# OmniLight.net
KiCad netlist of a schematic drawn in EAGLE
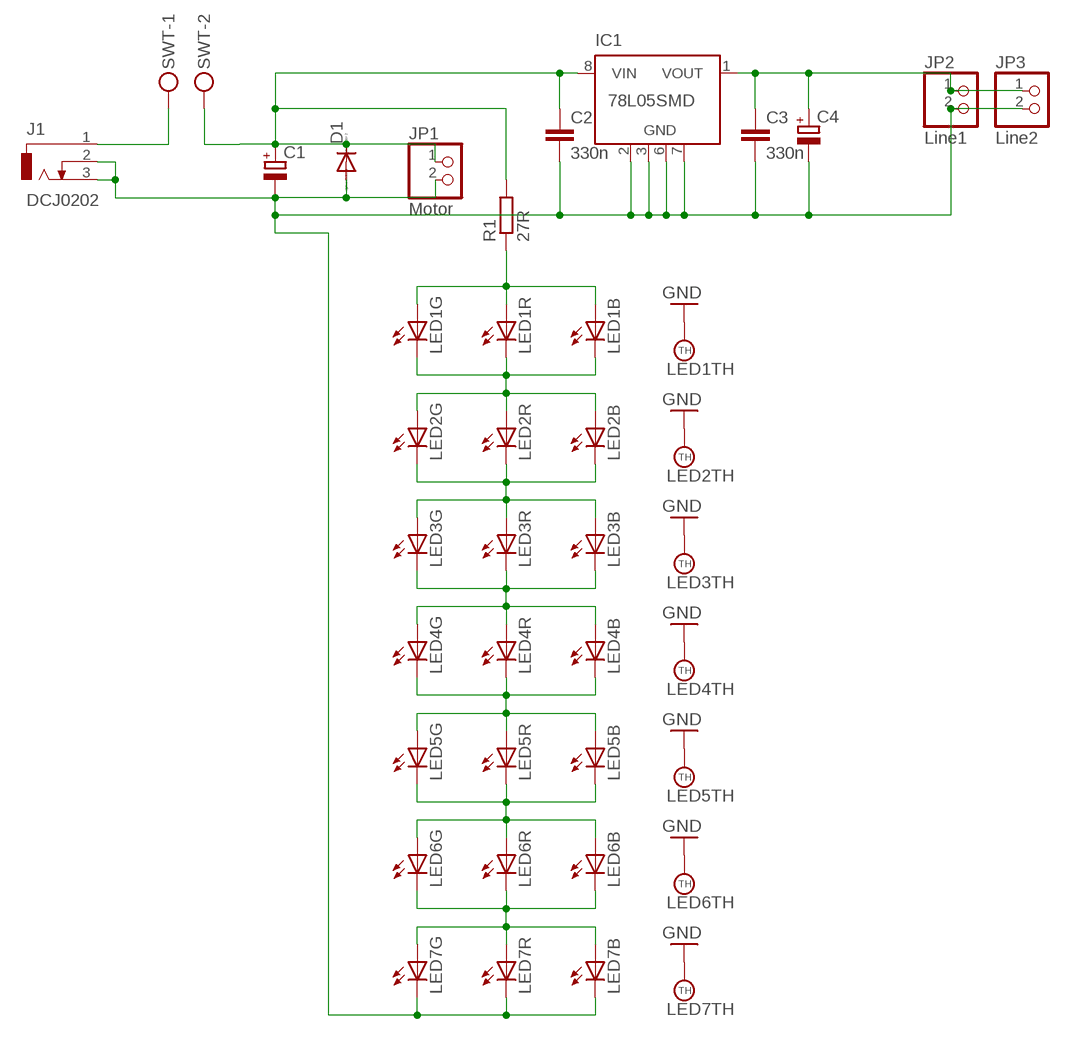
[diagram p0: schematic, sheet 1]

(export (version "E")
  (design (tool "Eeschema 10.0.6"))
  (components
    (comp (ref "C1")
      (value "CPOL-EU140CLH-0810")
      (footprint "eagle-import:140CLH-0810")
      (libsource (lib "eagle-import") (part "CPOL-EU140CLH-0810"))
    )
    (comp (ref "C2")
      (value "330n")
      (footprint "eagle-import:C1206")
      (libsource (lib "eagle-import") (part "C-EUC1206"))
    )
    (comp (ref "C3")
      (value "330n")
      (footprint "eagle-import:C1206")
      (libsource (lib "eagle-import") (part "C-EUC1206"))
    )
    (comp (ref "C4")
      (value "CPOL-EU140CLH-0810")
      (footprint "eagle-import:140CLH-0810")
      (libsource (lib "eagle-import") (part "CPOL-EU140CLH-0810"))
    )
    (comp (ref "D1")
      (value "DIODE-DO214AC")
      (footprint "eagle-import:DO214AC")
      (libsource (lib "eagle-import") (part "DIODE-DO214AC"))
    )
    (comp (ref "IC1")
      (value "78L05SMD")
      (footprint "eagle-import:SO08")
      (libsource (lib "eagle-import") (part "78LSMD05"))
    )
    (comp (ref "J1")
      (value "DCJ0202")
      (footprint "eagle-import:DCJ0202")
      (libsource (lib "eagle-import") (part "DCJ0202"))
    )
    (comp (ref "JP1")
      (value "Motor")
      (footprint "eagle-import:1X02")
      (libsource (lib "eagle-import") (part "PINHD-1X2"))
    )
    (comp (ref "JP2")
      (value "Line1")
      (footprint "eagle-import:1X02")
      (libsource (lib "eagle-import") (part "PINHD-1X2"))
    )
    (comp (ref "JP3")
      (value "Line2")
      (footprint "eagle-import:1X02")
      (libsource (lib "eagle-import") (part "PINHD-1X2"))
    )
    (comp (ref "LED1")
      (value "LP2C63-ST-RGB-SR0")
      (footprint "eagle-import:LP2C63-ST-RGB-SR0")
      (libsource (lib "eagle-import") (part "LP2C63-ST-RGB-SR0"))
    )
    (comp (ref "LED2")
      (value "LP2C63-ST-RGB-SR0")
      (footprint "eagle-import:LP2C63-ST-RGB-SR0")
      (libsource (lib "eagle-import") (part "LP2C63-ST-RGB-SR0"))
    )
    (comp (ref "LED3")
      (value "LP2C63-ST-RGB-SR0")
      (footprint "eagle-import:LP2C63-ST-RGB-SR0")
      (libsource (lib "eagle-import") (part "LP2C63-ST-RGB-SR0"))
    )
    (comp (ref "LED4")
      (value "LP2C63-ST-RGB-SR0")
      (footprint "eagle-import:LP2C63-ST-RGB-SR0")
      (libsource (lib "eagle-import") (part "LP2C63-ST-RGB-SR0"))
    )
    (comp (ref "LED5")
      (value "LP2C63-ST-RGB-SR0")
      (footprint "eagle-import:LP2C63-ST-RGB-SR0")
      (libsource (lib "eagle-import") (part "LP2C63-ST-RGB-SR0"))
    )
    (comp (ref "LED6")
      (value "LP2C63-ST-RGB-SR0")
      (footprint "eagle-import:LP2C63-ST-RGB-SR0")
      (libsource (lib "eagle-import") (part "LP2C63-ST-RGB-SR0"))
    )
    (comp (ref "LED7")
      (value "LP2C63-ST-RGB-SR0")
      (footprint "eagle-import:LP2C63-ST-RGB-SR0")
      (libsource (lib "eagle-import") (part "LP2C63-ST-RGB-SR0"))
    )
    (comp (ref "R1")
      (value "27R")
      (footprint "eagle-import:R1206")
      (libsource (lib "eagle-import") (part "R-EU_R1206"))
    )
    (comp (ref "SWT")
      (value "MKDSN1,5/2-5,08")
      (footprint "eagle-import:MKDSN1,5_2-5,08")
      (libsource (lib "eagle-import") (part "MKDSN1,5/2-5,08"))
    )
  )
  (nets
    (net (code "1") (name "GND") (class "Default")
      (node (ref "LED1") (pin "TH") (pinfunction "TH_TH") (pintype "passive"))
      (node (ref "LED2") (pin "TH") (pinfunction "TH_TH") (pintype "passive"))
      (node (ref "LED3") (pin "TH") (pinfunction "TH_TH") (pintype "passive"))
      (node (ref "LED4") (pin "TH") (pinfunction "TH_TH") (pintype "passive"))
      (node (ref "LED5") (pin "TH") (pinfunction "TH_TH") (pintype "passive"))
      (node (ref "LED6") (pin "TH") (pinfunction "TH_TH") (pintype "passive"))
      (node (ref "LED7") (pin "TH") (pinfunction "TH_TH") (pintype "passive"))
    )
    (net (code "2") (name "Net-(IC1A-VIN)") (class "Default")
      (node (ref "C1") (pin "+") (pinfunction "+_+") (pintype "passive"))
      (node (ref "C2") (pin "1") (pinfunction "1_1") (pintype "passive"))
      (node (ref "D1") (pin "C") (pinfunction "C_C") (pintype "passive"))
      (node (ref "IC1") (pin "8") (pinfunction "VIN_8") (pintype "passive"))
      (node (ref "JP1") (pin "1") (pinfunction "1_1") (pintype "passive"))
      (node (ref "R1") (pin "2") (pinfunction "2_2") (pintype "passive"))
      (node (ref "SWT") (pin "2") (pinfunction "KL_2") (pintype "passive"))
    )
    (net (code "3") (name "Net-(IC1A-VOUT)") (class "Default")
      (node (ref "C3") (pin "1") (pinfunction "1_1") (pintype "passive"))
      (node (ref "C4") (pin "+") (pinfunction "+_+") (pintype "passive"))
      (node (ref "IC1") (pin "1") (pinfunction "VOUT_1") (pintype "output"))
      (node (ref "JP2") (pin "1") (pinfunction "1_1") (pintype "passive"))
      (node (ref "JP3") (pin "1") (pinfunction "1_1") (pintype "passive"))
    )
    (net (code "4") (name "Net-(LED1A-A)") (class "Default")
      (node (ref "LED1") (pin "1") (pinfunction "A_1") (pintype "passive"))
      (node (ref "LED1") (pin "2") (pinfunction "A_2") (pintype "passive"))
      (node (ref "LED1") (pin "3") (pinfunction "A_3") (pintype "passive"))
      (node (ref "R1") (pin "1") (pinfunction "1_1") (pintype "passive"))
    )
    (net (code "5") (name "Net-(LED1A-C)") (class "Default")
      (node (ref "LED1") (pin "4") (pinfunction "C_4") (pintype "passive"))
      (node (ref "LED1") (pin "5") (pinfunction "C_5") (pintype "passive"))
      (node (ref "LED1") (pin "6") (pinfunction "C_6") (pintype "passive"))
      (node (ref "LED2") (pin "1") (pinfunction "A_1") (pintype "passive"))
      (node (ref "LED2") (pin "2") (pinfunction "A_2") (pintype "passive"))
      (node (ref "LED2") (pin "3") (pinfunction "A_3") (pintype "passive"))
    )
    (net (code "6") (name "Net-(LED2A-C)") (class "Default")
      (node (ref "LED2") (pin "4") (pinfunction "C_4") (pintype "passive"))
      (node (ref "LED2") (pin "5") (pinfunction "C_5") (pintype "passive"))
      (node (ref "LED2") (pin "6") (pinfunction "C_6") (pintype "passive"))
      (node (ref "LED3") (pin "1") (pinfunction "A_1") (pintype "passive"))
      (node (ref "LED3") (pin "2") (pinfunction "A_2") (pintype "passive"))
      (node (ref "LED3") (pin "3") (pinfunction "A_3") (pintype "passive"))
    )
    (net (code "7") (name "Net-(LED3A-C)") (class "Default")
      (node (ref "LED3") (pin "4") (pinfunction "C_4") (pintype "passive"))
      (node (ref "LED3") (pin "5") (pinfunction "C_5") (pintype "passive"))
      (node (ref "LED3") (pin "6") (pinfunction "C_6") (pintype "passive"))
      (node (ref "LED4") (pin "1") (pinfunction "A_1") (pintype "passive"))
      (node (ref "LED4") (pin "2") (pinfunction "A_2") (pintype "passive"))
      (node (ref "LED4") (pin "3") (pinfunction "A_3") (pintype "passive"))
    )
    (net (code "8") (name "Net-(LED4A-C)") (class "Default")
      (node (ref "LED4") (pin "4") (pinfunction "C_4") (pintype "passive"))
      (node (ref "LED4") (pin "5") (pinfunction "C_5") (pintype "passive"))
      (node (ref "LED4") (pin "6") (pinfunction "C_6") (pintype "passive"))
      (node (ref "LED5") (pin "1") (pinfunction "A_1") (pintype "passive"))
      (node (ref "LED5") (pin "2") (pinfunction "A_2") (pintype "passive"))
      (node (ref "LED5") (pin "3") (pinfunction "A_3") (pintype "passive"))
    )
    (net (code "9") (name "Net-(LED5A-C)") (class "Default")
      (node (ref "LED5") (pin "4") (pinfunction "C_4") (pintype "passive"))
      (node (ref "LED5") (pin "5") (pinfunction "C_5") (pintype "passive"))
      (node (ref "LED5") (pin "6") (pinfunction "C_6") (pintype "passive"))
      (node (ref "LED6") (pin "1") (pinfunction "A_1") (pintype "passive"))
      (node (ref "LED6") (pin "2") (pinfunction "A_2") (pintype "passive"))
      (node (ref "LED6") (pin "3") (pinfunction "A_3") (pintype "passive"))
    )
    (net (code "10") (name "Net-(LED6A-C)") (class "Default")
      (node (ref "LED6") (pin "4") (pinfunction "C_4") (pintype "passive"))
      (node (ref "LED6") (pin "5") (pinfunction "C_5") (pintype "passive"))
      (node (ref "LED6") (pin "6") (pinfunction "C_6") (pintype "passive"))
      (node (ref "LED7") (pin "1") (pinfunction "A_1") (pintype "passive"))
      (node (ref "LED7") (pin "2") (pinfunction "A_2") (pintype "passive"))
      (node (ref "LED7") (pin "3") (pinfunction "A_3") (pintype "passive"))
    )
    (net (code "11") (name "Net-(LED7A-C)") (class "Default")
      (node (ref "C1") (pin "-") (pinfunction "-_-") (pintype "passive"))
      (node (ref "C2") (pin "2") (pinfunction "2_2") (pintype "passive"))
      (node (ref "C3") (pin "2") (pinfunction "2_2") (pintype "passive"))
      (node (ref "C4") (pin "-") (pinfunction "-_-") (pintype "passive"))
      (node (ref "D1") (pin "A") (pinfunction "A_A") (pintype "passive"))
      (node (ref "IC1") (pin "2") (pinfunction "GND_2") (pintype "power_in"))
      (node (ref "IC1") (pin "3") (pinfunction "GND_3") (pintype "power_in"))
      (node (ref "IC1") (pin "6") (pinfunction "GND_6") (pintype "power_in"))
      (node (ref "IC1") (pin "7") (pinfunction "GND_7") (pintype "power_in"))
      (node (ref "J1") (pin "2") (pinfunction "2_2") (pintype "passive"))
      (node (ref "J1") (pin "3") (pinfunction "3_3") (pintype "passive"))
      (node (ref "JP1") (pin "2") (pinfunction "2_2") (pintype "passive"))
      (node (ref "JP2") (pin "2") (pinfunction "2_2") (pintype "passive"))
      (node (ref "JP3") (pin "2") (pinfunction "2_2") (pintype "passive"))
      (node (ref "LED7") (pin "4") (pinfunction "C_4") (pintype "passive"))
      (node (ref "LED7") (pin "5") (pinfunction "C_5") (pintype "passive"))
      (node (ref "LED7") (pin "6") (pinfunction "C_6") (pintype "passive"))
    )
    (net (code "12") (name "Net-(SWTA-KL)") (class "Default")
      (node (ref "J1") (pin "1") (pinfunction "1_1") (pintype "passive"))
      (node (ref "SWT") (pin "1") (pinfunction "KL_1") (pintype "passive"))
    )
  )
)
